# Sano_LEGO.net
KiCad netlist of a schematic drawn in EAGLE
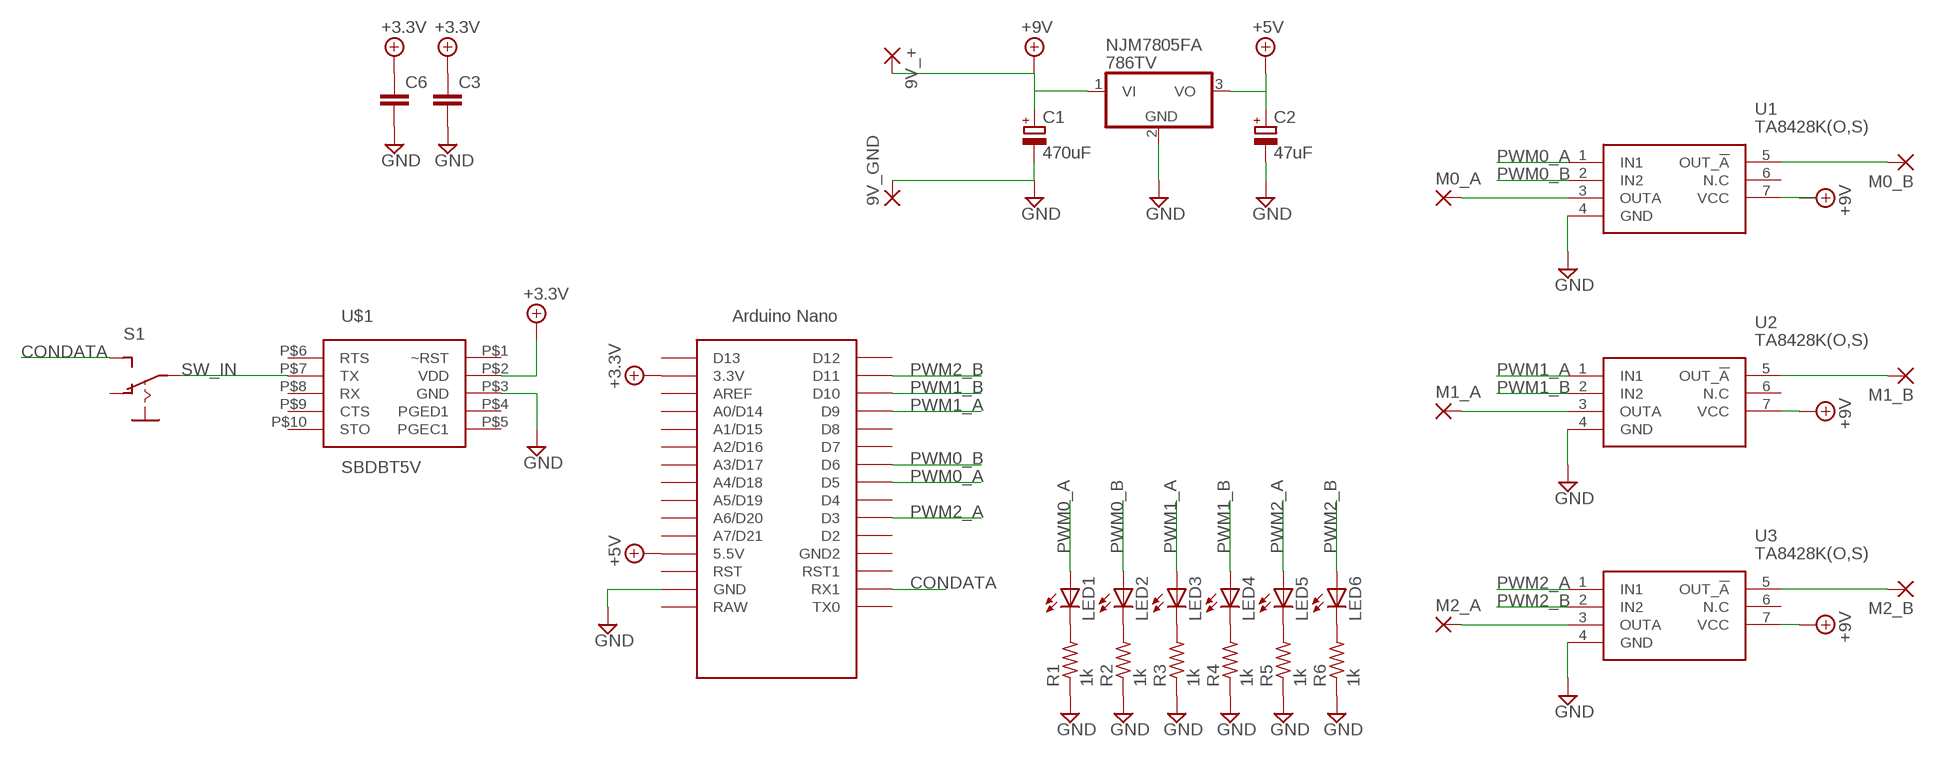
[diagram p0: schematic, sheet 1]

(export (version "E")
  (design (tool "Eeschema 10.0.6"))
  (components
    (comp (ref "9V_+")
      (value "3,81/1,4")
      (footprint "eagle-import:3,81_1,4")
      (libsource (lib "eagle-import") (part "3,81/1,4"))
    )
    (comp (ref "9V_GND")
      (value "3,81/1,4")
      (footprint "eagle-import:3,81_1,4")
      (libsource (lib "eagle-import") (part "3,81/1,4"))
    )
    (comp (ref "C1")
      (value "470uF")
      (footprint "eagle-import:E3,5-10")
      (libsource (lib "eagle-import") (part "CPOL-EUE3.5-10"))
    )
    (comp (ref "C2")
      (value "47uF")
      (footprint "eagle-import:E2-5")
      (libsource (lib "eagle-import") (part "CPOL-EUE2-5"))
    )
    (comp (ref "C3")
      (value "C-EU025-025X050")
      (footprint "eagle-import:C025-025X050")
      (libsource (lib "eagle-import") (part "C-EU025-025X050"))
    )
    (comp (ref "C6")
      (value "C-EU025-025X050")
      (footprint "eagle-import:C025-025X050")
      (libsource (lib "eagle-import") (part "C-EU025-025X050"))
    )
    (comp (ref "LED1")
      (value "LED3MM")
      (footprint "eagle-import:LED3MM")
      (libsource (lib "eagle-import") (part "LED3MM"))
    )
    (comp (ref "LED2")
      (value "LED3MM")
      (footprint "eagle-import:LED3MM")
      (libsource (lib "eagle-import") (part "LED3MM"))
    )
    (comp (ref "LED3")
      (value "LED3MM")
      (footprint "eagle-import:LED3MM")
      (libsource (lib "eagle-import") (part "LED3MM"))
    )
    (comp (ref "LED4")
      (value "LED3MM")
      (footprint "eagle-import:LED3MM")
      (libsource (lib "eagle-import") (part "LED3MM"))
    )
    (comp (ref "LED5")
      (value "LED3MM")
      (footprint "eagle-import:LED3MM")
      (libsource (lib "eagle-import") (part "LED3MM"))
    )
    (comp (ref "LED6")
      (value "LED3MM")
      (footprint "eagle-import:LED3MM")
      (libsource (lib "eagle-import") (part "LED3MM"))
    )
    (comp (ref "M0_A")
      (value "3,81/1,4")
      (footprint "eagle-import:3,81_1,4")
      (libsource (lib "eagle-import") (part "3,81/1,4"))
    )
    (comp (ref "M0_B")
      (value "3,81/1,4")
      (footprint "eagle-import:3,81_1,4")
      (libsource (lib "eagle-import") (part "3,81/1,4"))
    )
    (comp (ref "M1_A")
      (value "3,81/1,4")
      (footprint "eagle-import:3,81_1,4")
      (libsource (lib "eagle-import") (part "3,81/1,4"))
    )
    (comp (ref "M1_B")
      (value "3,81/1,4")
      (footprint "eagle-import:3,81_1,4")
      (libsource (lib "eagle-import") (part "3,81/1,4"))
    )
    (comp (ref "M2_A")
      (value "3,81/1,4")
      (footprint "eagle-import:3,81_1,4")
      (libsource (lib "eagle-import") (part "3,81/1,4"))
    )
    (comp (ref "M2_B")
      (value "3,81/1,4")
      (footprint "eagle-import:3,81_1,4")
      (libsource (lib "eagle-import") (part "3,81/1,4"))
    )
    (comp (ref "NJM7805FA")
      (value "786TV")
      (footprint "eagle-import:TO220V")
      (libsource (lib "eagle-import") (part "78TV6"))
    )
    (comp (ref "R1")
      (value "1k")
      (footprint "eagle-import:R1608")
      (libsource (lib "eagle-import") (part "R-US_R1608"))
    )
    (comp (ref "R2")
      (value "1k")
      (footprint "eagle-import:R1608")
      (libsource (lib "eagle-import") (part "R-US_R1608"))
    )
    (comp (ref "R3")
      (value "1k")
      (footprint "eagle-import:R1608")
      (libsource (lib "eagle-import") (part "R-US_R1608"))
    )
    (comp (ref "R4")
      (value "1k")
      (footprint "eagle-import:R1608")
      (libsource (lib "eagle-import") (part "R-US_R1608"))
    )
    (comp (ref "R5")
      (value "1k")
      (footprint "eagle-import:R1608")
      (libsource (lib "eagle-import") (part "R-US_R1608"))
    )
    (comp (ref "R6")
      (value "1k")
      (footprint "eagle-import:R1608")
      (libsource (lib "eagle-import") (part "R-US_R1608"))
    )
    (comp (ref "S1")
      (value "S-SWITCHSMALL")
      (footprint "eagle-import:DS")
      (libsource (lib "eagle-import") (part "S-SWITCHSMALL"))
    )
    (comp (ref "U$1")
      (value "SBDBT5V")
      (footprint "eagle-import:SBDBT")
      (libsource (lib "eagle-import") (part "SBDBT5V"))
    )
    (comp (ref "U$2")
      (value "NANO")
      (footprint "eagle-import:NANO")
      (libsource (lib "eagle-import") (part "NANO"))
    )
    (comp (ref "U1")
      (value "TA8428K(O,S)")
      (footprint "eagle-import:HSIP7-P-2.54_1")
      (fields (field (name "RS_PART_NUMBER") "6939336"))
      (libsource (lib "eagle-import") (part "TA8428K(O,S)"))
    )
    (comp (ref "U2")
      (value "TA8428K(O,S)")
      (footprint "eagle-import:HSIP7-P-2.54_1")
      (fields (field (name "RS_PART_NUMBER") "6939336"))
      (libsource (lib "eagle-import") (part "TA8428K(O,S)"))
    )
    (comp (ref "U3")
      (value "TA8428K(O,S)")
      (footprint "eagle-import:HSIP7-P-2.54_1")
      (fields (field (name "RS_PART_NUMBER") "6939336"))
      (libsource (lib "eagle-import") (part "TA8428K(O,S)"))
    )
  )
  (nets
    (net (code "1") (name "+3.3V") (class "Default")
      (node (ref "C3") (pin "1") (pinfunction "1_1") (pintype "passive"))
      (node (ref "C6") (pin "1") (pinfunction "1_1") (pintype "passive"))
      (node (ref "U$1") (pin "P$2") (pinfunction "VDD_P$2") (pintype "bidirectional"))
      (node (ref "U$2") (pin "3.3V") (pinfunction "3.3V_3.3V") (pintype "bidirectional"))
    )
    (net (code "2") (name "+5V") (class "Default")
      (node (ref "C2") (pin "+") (pinfunction "+_+") (pintype "passive"))
      (node (ref "NJM7805FA") (pin "3") (pinfunction "VO_3") (pintype "passive"))
      (node (ref "U$2") (pin "5V") (pinfunction "5.5V_5V") (pintype "bidirectional"))
    )
    (net (code "3") (name "+9V") (class "Default")
      (node (ref "9V_+") (pin "1") (pinfunction "P_1") (pintype "passive"))
      (node (ref "C1") (pin "+") (pinfunction "+_+") (pintype "passive"))
      (node (ref "NJM7805FA") (pin "1") (pinfunction "VI_1") (pintype "input"))
      (node (ref "U1") (pin "7") (pinfunction "VCC_7") (pintype "bidirectional"))
      (node (ref "U2") (pin "7") (pinfunction "VCC_7") (pintype "bidirectional"))
      (node (ref "U3") (pin "7") (pinfunction "VCC_7") (pintype "bidirectional"))
    )
    (net (code "4") (name "/CONDATA") (class "Default")
      (node (ref "S1") (pin "P$3") (pinfunction "S_P$3") (pintype "passive"))
      (node (ref "U$2") (pin "RX1") (pinfunction "RX1_RX1") (pintype "bidirectional"))
    )
    (net (code "5") (name "/PWM0_A") (class "Default")
      (node (ref "LED1") (pin "A") (pinfunction "A_A") (pintype "passive"))
      (node (ref "U$2") (pin "D5") (pinfunction "D5_D5") (pintype "bidirectional"))
      (node (ref "U1") (pin "1") (pinfunction "IN1_1") (pintype "bidirectional"))
    )
    (net (code "6") (name "/PWM0_B") (class "Default")
      (node (ref "LED2") (pin "A") (pinfunction "A_A") (pintype "passive"))
      (node (ref "U$2") (pin "D6") (pinfunction "D6_D6") (pintype "bidirectional"))
      (node (ref "U1") (pin "2") (pinfunction "IN2_2") (pintype "bidirectional"))
    )
    (net (code "7") (name "/PWM1_A") (class "Default")
      (node (ref "LED3") (pin "A") (pinfunction "A_A") (pintype "passive"))
      (node (ref "U$2") (pin "D9") (pinfunction "D9_D9") (pintype "bidirectional"))
      (node (ref "U2") (pin "1") (pinfunction "IN1_1") (pintype "bidirectional"))
    )
    (net (code "8") (name "/PWM1_B") (class "Default")
      (node (ref "LED4") (pin "A") (pinfunction "A_A") (pintype "passive"))
      (node (ref "U$2") (pin "D10") (pinfunction "D10_D10") (pintype "bidirectional"))
      (node (ref "U2") (pin "2") (pinfunction "IN2_2") (pintype "bidirectional"))
    )
    (net (code "9") (name "/PWM2_A") (class "Default")
      (node (ref "LED5") (pin "A") (pinfunction "A_A") (pintype "passive"))
      (node (ref "U$2") (pin "D3") (pinfunction "D3_D3") (pintype "bidirectional"))
      (node (ref "U3") (pin "1") (pinfunction "IN1_1") (pintype "bidirectional"))
    )
    (net (code "10") (name "/PWM2_B") (class "Default")
      (node (ref "LED6") (pin "A") (pinfunction "A_A") (pintype "passive"))
      (node (ref "U$2") (pin "D11") (pinfunction "D11_D11") (pintype "bidirectional"))
      (node (ref "U3") (pin "2") (pinfunction "IN2_2") (pintype "bidirectional"))
    )
    (net (code "11") (name "/SW_IN") (class "Default")
      (node (ref "S1") (pin "P$2") (pinfunction "P_P$2") (pintype "passive"))
      (node (ref "U$1") (pin "P$7") (pinfunction "TX_P$7") (pintype "bidirectional"))
    )
    (net (code "12") (name "GND") (class "Default")
      (node (ref "9V_GND") (pin "1") (pinfunction "P_1") (pintype "passive"))
      (node (ref "C1") (pin "-") (pinfunction "-_-") (pintype "passive"))
      (node (ref "C2") (pin "-") (pinfunction "-_-") (pintype "passive"))
      (node (ref "C3") (pin "2") (pinfunction "2_2") (pintype "passive"))
      (node (ref "C6") (pin "2") (pinfunction "2_2") (pintype "passive"))
      (node (ref "NJM7805FA") (pin "2") (pinfunction "GND_2") (pintype "passive"))
      (node (ref "R1") (pin "1") (pinfunction "1_1") (pintype "passive"))
      (node (ref "R2") (pin "1") (pinfunction "1_1") (pintype "passive"))
      (node (ref "R3") (pin "1") (pinfunction "1_1") (pintype "passive"))
      (node (ref "R4") (pin "1") (pinfunction "1_1") (pintype "passive"))
      (node (ref "R5") (pin "1") (pinfunction "1_1") (pintype "passive"))
      (node (ref "R6") (pin "1") (pinfunction "1_1") (pintype "passive"))
      (node (ref "U$1") (pin "P$3") (pinfunction "GND_P$3") (pintype "bidirectional"))
      (node (ref "U$2") (pin "GND") (pinfunction "GND_GND") (pintype "bidirectional"))
      (node (ref "U1") (pin "4") (pinfunction "GND_4") (pintype "bidirectional"))
      (node (ref "U2") (pin "4") (pinfunction "GND_4") (pintype "bidirectional"))
      (node (ref "U3") (pin "4") (pinfunction "GND_4") (pintype "bidirectional"))
    )
    (net (code "13") (name "Net-(LED1-C)") (class "Default")
      (node (ref "LED1") (pin "K") (pinfunction "C_K") (pintype "passive"))
      (node (ref "R1") (pin "2") (pinfunction "2_2") (pintype "passive"))
    )
    (net (code "14") (name "Net-(LED2-C)") (class "Default")
      (node (ref "LED2") (pin "K") (pinfunction "C_K") (pintype "passive"))
      (node (ref "R2") (pin "2") (pinfunction "2_2") (pintype "passive"))
    )
    (net (code "15") (name "Net-(LED3-C)") (class "Default")
      (node (ref "LED3") (pin "K") (pinfunction "C_K") (pintype "passive"))
      (node (ref "R3") (pin "2") (pinfunction "2_2") (pintype "passive"))
    )
    (net (code "16") (name "Net-(LED4-C)") (class "Default")
      (node (ref "LED4") (pin "K") (pinfunction "C_K") (pintype "passive"))
      (node (ref "R4") (pin "2") (pinfunction "2_2") (pintype "passive"))
    )
    (net (code "17") (name "Net-(LED5-C)") (class "Default")
      (node (ref "LED5") (pin "K") (pinfunction "C_K") (pintype "passive"))
      (node (ref "R5") (pin "2") (pinfunction "2_2") (pintype "passive"))
    )
    (net (code "18") (name "Net-(LED6-C)") (class "Default")
      (node (ref "LED6") (pin "K") (pinfunction "C_K") (pintype "passive"))
      (node (ref "R6") (pin "2") (pinfunction "2_2") (pintype "passive"))
    )
    (net (code "19") (name "Net-(M0_A-P)") (class "Default")
      (node (ref "M0_A") (pin "1") (pinfunction "P_1") (pintype "passive"))
      (node (ref "U1") (pin "3") (pinfunction "OUTA_3") (pintype "bidirectional"))
    )
    (net (code "20") (name "Net-(M0_B-P)") (class "Default")
      (node (ref "M0_B") (pin "1") (pinfunction "P_1") (pintype "passive"))
      (node (ref "U1") (pin "5") (pinfunction "OUT_~{A}_5") (pintype "bidirectional"))
    )
    (net (code "21") (name "Net-(M1_A-P)") (class "Default")
      (node (ref "M1_A") (pin "1") (pinfunction "P_1") (pintype "passive"))
      (node (ref "U2") (pin "3") (pinfunction "OUTA_3") (pintype "bidirectional"))
    )
    (net (code "22") (name "Net-(M1_B-P)") (class "Default")
      (node (ref "M1_B") (pin "1") (pinfunction "P_1") (pintype "passive"))
      (node (ref "U2") (pin "5") (pinfunction "OUT_~{A}_5") (pintype "bidirectional"))
    )
    (net (code "23") (name "Net-(M2_A-P)") (class "Default")
      (node (ref "M2_A") (pin "1") (pinfunction "P_1") (pintype "passive"))
      (node (ref "U3") (pin "3") (pinfunction "OUTA_3") (pintype "bidirectional"))
    )
    (net (code "24") (name "Net-(M2_B-P)") (class "Default")
      (node (ref "M2_B") (pin "1") (pinfunction "P_1") (pintype "passive"))
      (node (ref "U3") (pin "5") (pinfunction "OUT_~{A}_5") (pintype "bidirectional"))
    )
    (net (code "25") (name "unconnected-(S1-O-PadP$1)") (class "Default")
      (node (ref "S1") (pin "P$1") (pinfunction "O_P$1") (pintype "passive"))
    )
    (net (code "26") (name "unconnected-(U$1-CTS-PadP$9)") (class "Default")
      (node (ref "U$1") (pin "P$9") (pinfunction "CTS_P$9") (pintype "bidirectional"))
    )
    (net (code "27") (name "unconnected-(U$1-PGEC1-PadP$5)") (class "Default")
      (node (ref "U$1") (pin "P$5") (pinfunction "PGEC1_P$5") (pintype "bidirectional"))
    )
    (net (code "28") (name "unconnected-(U$1-PGED1-PadP$4)") (class "Default")
      (node (ref "U$1") (pin "P$4") (pinfunction "PGED1_P$4") (pintype "bidirectional"))
    )
    (net (code "29") (name "unconnected-(U$1-RTS-PadP$6)") (class "Default")
      (node (ref "U$1") (pin "P$6") (pinfunction "RTS_P$6") (pintype "bidirectional"))
    )
    (net (code "30") (name "unconnected-(U$1-RX-PadP$8)") (class "Default")
      (node (ref "U$1") (pin "P$8") (pinfunction "RX_P$8") (pintype "bidirectional"))
    )
    (net (code "31") (name "unconnected-(U$1-STO-PadP$10)") (class "Default")
      (node (ref "U$1") (pin "P$10") (pinfunction "STO_P$10") (pintype "bidirectional"))
    )
    (net (code "32") (name "unconnected-(U$1-~{RST}-PadP$1)") (class "Default")
      (node (ref "U$1") (pin "P$1") (pinfunction "~{RST}_P$1") (pintype "bidirectional"))
    )
    (net (code "33") (name "unconnected-(U$2-A0{slash}D14-PadA0)") (class "Default")
      (node (ref "U$2") (pin "A0") (pinfunction "A0/D14_A0") (pintype "bidirectional"))
    )
    (net (code "34") (name "unconnected-(U$2-A1{slash}D15-PadA1)") (class "Default")
      (node (ref "U$2") (pin "A1") (pinfunction "A1/D15_A1") (pintype "bidirectional"))
    )
    (net (code "35") (name "unconnected-(U$2-A2{slash}D16-PadA2)") (class "Default")
      (node (ref "U$2") (pin "A2") (pinfunction "A2/D16_A2") (pintype "bidirectional"))
    )
    (net (code "36") (name "unconnected-(U$2-A3{slash}D17-PadA3)") (class "Default")
      (node (ref "U$2") (pin "A3") (pinfunction "A3/D17_A3") (pintype "bidirectional"))
    )
    (net (code "37") (name "unconnected-(U$2-A4{slash}D18-PadA4)") (class "Default")
      (node (ref "U$2") (pin "A4") (pinfunction "A4/D18_A4") (pintype "bidirectional"))
    )
    (net (code "38") (name "unconnected-(U$2-A5{slash}D19-PadA5)") (class "Default")
      (node (ref "U$2") (pin "A5") (pinfunction "A5/D19_A5") (pintype "bidirectional"))
    )
    (net (code "39") (name "unconnected-(U$2-A6{slash}D20-PadA6)") (class "Default")
      (node (ref "U$2") (pin "A6") (pinfunction "A6/D20_A6") (pintype "bidirectional"))
    )
    (net (code "40") (name "unconnected-(U$2-A7{slash}D21-PadA7)") (class "Default")
      (node (ref "U$2") (pin "A7") (pinfunction "A7/D21_A7") (pintype "bidirectional"))
    )
    (net (code "41") (name "unconnected-(U$2-GND2-PadGND1)") (class "Default")
      (node (ref "U$2") (pin "GND1") (pinfunction "GND2_GND1") (pintype "bidirectional"))
    )
    (net (code "42") (name "unconnected-(U$2-PadAREF)") (class "Default")
      (node (ref "U$2") (pin "AREF") (pinfunction "AREF_AREF") (pintype "bidirectional"))
    )
    (net (code "43") (name "unconnected-(U$2-PadD2)") (class "Default")
      (node (ref "U$2") (pin "D2") (pinfunction "D2_D2") (pintype "bidirectional"))
    )
    (net (code "44") (name "unconnected-(U$2-PadD4)") (class "Default")
      (node (ref "U$2") (pin "D4") (pinfunction "D4_D4") (pintype "bidirectional"))
    )
    (net (code "45") (name "unconnected-(U$2-PadD7)") (class "Default")
      (node (ref "U$2") (pin "D7") (pinfunction "D7_D7") (pintype "bidirectional"))
    )
    (net (code "46") (name "unconnected-(U$2-PadD8)") (class "Default")
      (node (ref "U$2") (pin "D8") (pinfunction "D8_D8") (pintype "bidirectional"))
    )
    (net (code "47") (name "unconnected-(U$2-PadD12)") (class "Default")
      (node (ref "U$2") (pin "D12") (pinfunction "D12_D12") (pintype "bidirectional"))
    )
    (net (code "48") (name "unconnected-(U$2-PadD13)") (class "Default")
      (node (ref "U$2") (pin "D13") (pinfunction "D13_D13") (pintype "bidirectional"))
    )
    (net (code "49") (name "unconnected-(U$2-PadRAW)") (class "Default")
      (node (ref "U$2") (pin "RAW") (pinfunction "RAW_RAW") (pintype "bidirectional"))
    )
    (net (code "50") (name "unconnected-(U$2-PadRST)") (class "Default")
      (node (ref "U$2") (pin "RST") (pinfunction "RST_RST") (pintype "bidirectional"))
    )
    (net (code "51") (name "unconnected-(U$2-PadRST1)") (class "Default")
      (node (ref "U$2") (pin "RST1") (pinfunction "RST1_RST1") (pintype "bidirectional"))
    )
    (net (code "52") (name "unconnected-(U$2-PadTX0)") (class "Default")
      (node (ref "U$2") (pin "TX0") (pinfunction "TX0_TX0") (pintype "bidirectional"))
    )
    (net (code "53") (name "unconnected-(U1-N.C-Pad6)") (class "Default")
      (node (ref "U1") (pin "6") (pinfunction "N.C_6") (pintype "no_connect"))
    )
    (net (code "54") (name "unconnected-(U2-N.C-Pad6)") (class "Default")
      (node (ref "U2") (pin "6") (pinfunction "N.C_6") (pintype "no_connect"))
    )
    (net (code "55") (name "unconnected-(U3-N.C-Pad6)") (class "Default")
      (node (ref "U3") (pin "6") (pinfunction "N.C_6") (pintype "no_connect"))
    )
  )
)
